# Sheet5.net
KiCad netlist of a schematic drawn in Altium Designer
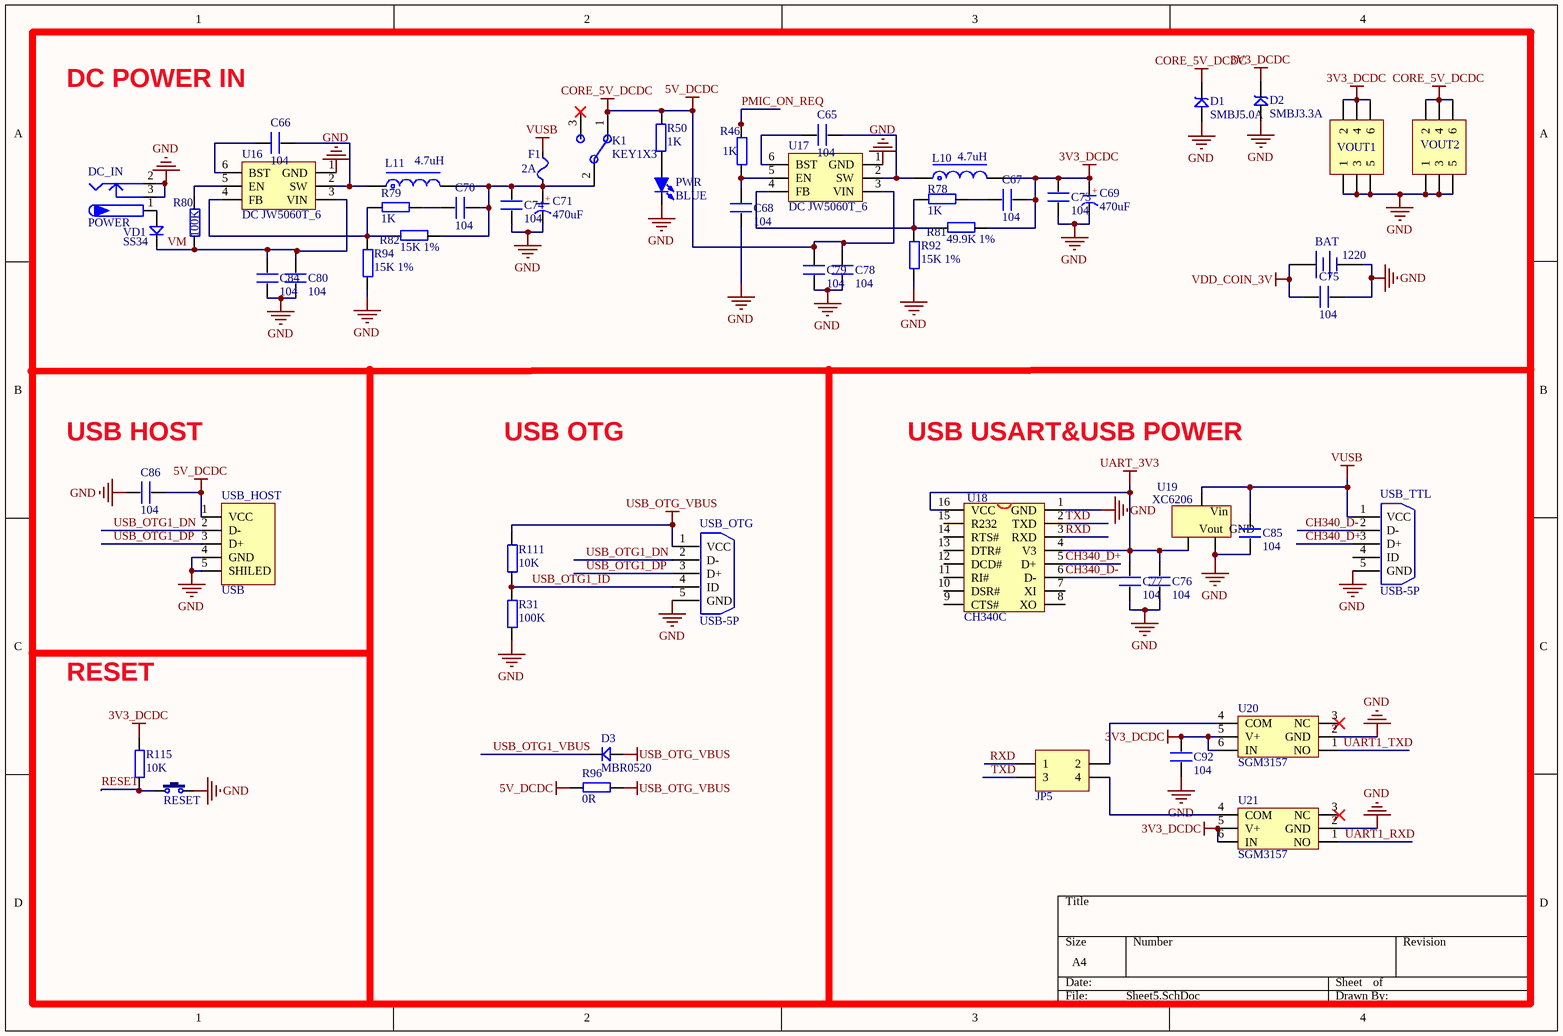
[diagram p0: Sheet5.SchDoc]

(export (version "E")
  (design (tool "Eeschema 10.0.6"))
  (components
    (comp (ref "BAT")
      (value "1220")
      (footprint "CR1220_B")
      (description "微型电池")
      (fields (field (name "版权归属") "源创客"))
      (libsource (lib "linux_board_SCH") (part "CR-3V"))
    )
    (comp (ref "C65") (value "104") (footprint "C 0603") (libsource (lib "linux_board_SCH") (part "C")))
    (comp (ref "C66") (value "104") (footprint "C 0603") (libsource (lib "linux_board_SCH") (part "C")))
    (comp (ref "C67") (value "104") (footprint "C 0603") (libsource (lib "linux_board_SCH") (part "C")))
    (comp (ref "C68") (value "104") (footprint "C 0603") (libsource (lib "linux_board_SCH") (part "C")))
    (comp (ref "C69")
      (value "470uF")
      (footprint "CM D(6.3*5.4)")
      (description "贴片电解电容")
      (fields (field (name "版权归属") "源创客"))
      (libsource (lib "linux_board_SCH") (part "C-CM"))
    )
    (comp (ref "C70") (value "104") (footprint "C 0603") (libsource (lib "linux_board_SCH") (part "C")))
    (comp (ref "C71")
      (value "470uF")
      (footprint "CM D(6.3*5.4)")
      (description "贴片电解电容")
      (fields (field (name "版权归属") "源创客"))
      (libsource (lib "linux_board_SCH") (part "C-CM"))
    )
    (comp (ref "C73") (value "104") (footprint "C 0603") (libsource (lib "linux_board_SCH") (part "C")))
    (comp (ref "C74") (value "104") (footprint "C 0603") (libsource (lib "linux_board_SCH") (part "C")))
    (comp (ref "C75") (value "104") (footprint "C 0603") (libsource (lib "linux_board_SCH") (part "C")))
    (comp (ref "C76") (value "104") (footprint "C 0603") (libsource (lib "linux_board_SCH") (part "C")))
    (comp (ref "C77") (value "104") (footprint "C 0603") (libsource (lib "linux_board_SCH") (part "C")))
    (comp (ref "C78") (value "104") (footprint "C 0603") (libsource (lib "linux_board_SCH") (part "C")))
    (comp (ref "C79") (value "104") (footprint "C 0603") (libsource (lib "linux_board_SCH") (part "C")))
    (comp (ref "C80") (value "104") (footprint "C 0603") (libsource (lib "linux_board_SCH") (part "C")))
    (comp (ref "C84") (value "104") (footprint "C 0603") (libsource (lib "linux_board_SCH") (part "C")))
    (comp (ref "C85") (value "104") (footprint "C 0603") (libsource (lib "linux_board_SCH") (part "C")))
    (comp (ref "C86") (value "104") (footprint "C 0603") (libsource (lib "linux_board_SCH") (part "C")))
    (comp (ref "C92") (value "104") (footprint "C 0603") (libsource (lib "linux_board_SCH") (part "C")))
    (comp (ref "D1")
      (value "SMBJ5.0A")
      (footprint "SMBJ")
      (description "TVS")
      (libsource (lib "linux_board_SCH") (part "SMBJ"))
    )
    (comp (ref "D2")
      (value "SMBJ3.3A")
      (footprint "SMBJ")
      (description "TVS")
      (libsource (lib "linux_board_SCH") (part "SMBJ"))
    )
    (comp (ref "D3")
      (value "MBR0520")
      (footprint "SOD-123F")
      (description "肖特基二极管")
      (fields (field (name "版权归属") "源创客"))
      (libsource (lib "linux_board_SCH") (part "SS14"))
    )
    (comp (ref "DC_IN")
      (value "POWER")
      (footprint "DC10B")
      (description "低压电源接口")
      (fields (field (name "版权归属") "源创客"))
      (libsource (lib "linux_board_SCH") (part "P-DC"))
    )
    (comp (ref "F1")
      (value "2A")
      (footprint "FU 1206")
      (description "贴片保险丝")
      (fields (field (name "版权归属") "源创客"))
      (libsource (lib "linux_board_SCH") (part "FU"))
    )
    (comp (ref "JP5")
      (value "Header2X2")
      (footprint "HDR-2X2")
      (description "2*2P接插件")
      (fields (field (name "版权归属") "源创客"))
      (libsource (lib "linux_board_SCH") (part "Header 2X2"))
    )
    (comp (ref "K1") (value "KEY1X3") (footprint "PKEY") (libsource (lib "linux_board_SCH") (part "PKEY")))
    (comp (ref "L10")
      (value "4.7uH")
      (footprint "L-SMD-0420")
      (description "功率屏蔽电感")
      (fields (field (name "版权归属") "源创客"))
      (libsource (lib "linux_board_SCH") (part "L-CDRH"))
    )
    (comp (ref "L11")
      (value "4.7uH")
      (footprint "L-SMD-0420")
      (description "功率屏蔽电感")
      (fields (field (name "版权归属") "源创客"))
      (libsource (lib "linux_board_SCH") (part "L-CDRH"))
    )
    (comp (ref "PWR")
      (value "BLUE")
      (footprint "LED 0805R")
      (description "贴片LED")
      (fields (field (name "版权归属") "源创客"))
      (libsource (lib "linux_board_SCH") (part "LED-SMD"))
    )
    (comp (ref "R31") (value "100K") (footprint "R 0603") (libsource (lib "linux_board_SCH") (part "R")))
    (comp (ref "R46") (value "1K") (footprint "R 0603") (libsource (lib "linux_board_SCH") (part "R")))
    (comp (ref "R50") (value "1K") (footprint "R 0603") (libsource (lib "linux_board_SCH") (part "R")))
    (comp (ref "R78") (value "1K") (footprint "R 0603") (libsource (lib "linux_board_SCH") (part "R")))
    (comp (ref "R79") (value "1K") (footprint "R 0603") (libsource (lib "linux_board_SCH") (part "R")))
    (comp (ref "R80") (value "100K") (footprint "R 0603") (libsource (lib "linux_board_SCH") (part "R")))
    (comp (ref "R81") (value "49.9K 1%") (footprint "R 0603") (libsource (lib "linux_board_SCH") (part "R")))
    (comp (ref "R82") (value "15K 1%") (footprint "R 0603") (libsource (lib "linux_board_SCH") (part "R")))
    (comp (ref "R92") (value "15K 1%") (footprint "R 0603") (libsource (lib "linux_board_SCH") (part "R")))
    (comp (ref "R94") (value "15K 1%") (footprint "R 0603") (libsource (lib "linux_board_SCH") (part "R")))
    (comp (ref "R96") (value "0R") (footprint "R 0603") (libsource (lib "linux_board_SCH") (part "R")))
    (comp (ref "R111") (value "10K") (footprint "R 0603") (libsource (lib "linux_board_SCH") (part "R")))
    (comp (ref "R115") (value "10K") (footprint "R 0603") (libsource (lib "linux_board_SCH") (part "R")))
    (comp (ref "RESET")
      (value "KEY")
      (footprint "TSW DIP-6*6*5 - 2")
      (description "按键")
      (fields (field (name "版权归属") "源创客"))
      (libsource (lib "linux_board_SCH") (part "KEY"))
    )
    (comp (ref "U16")
      (value "DC JW5060T_6")
      (footprint "SOT23-6N")
      (description "DC降压芯片")
      (libsource (lib "linux_board_SCH") (part "DC JW5060T_6"))
    )
    (comp (ref "U17")
      (value "DC JW5060T_6")
      (footprint "SOT23-6N")
      (description "DC降压芯片")
      (libsource (lib "linux_board_SCH") (part "DC JW5060T_6"))
    )
    (comp (ref "U18")
      (value "CH340C")
      (footprint "SOP16_N")
      (description "USB2UART")
      (libsource (lib "linux_board_SCH") (part "CH340G"))
    )
    (comp (ref "U19")
      (value "XC6206")
      (footprint "SOT23-3N")
      (description "LDO")
      (libsource (lib "linux_board_SCH") (part "LDO XC6206"))
    )
    (comp (ref "U20")
      (value "SGM3157")
      (footprint "SOT363-6L")
      (description "单路双掷模拟开关")
      (libsource (lib "linux_board_SCH") (part "SGM3157"))
    )
    (comp (ref "U21")
      (value "SGM3157")
      (footprint "SOT363-6L")
      (description "单路双掷模拟开关")
      (libsource (lib "linux_board_SCH") (part "SGM3157"))
    )
    (comp (ref "USB_HOST")
      (value "USB")
      (footprint "USB-A/S_E")
      (description "USB-A型母接口")
      (fields (field (name "版权归属") "源创客"))
      (libsource (lib "linux_board_SCH") (part "USB-A/S"))
    )
    (comp (ref "USB_OTG")
      (value "USB-5P")
      (footprint "USB-MINI-A")
      (description "微型USB母座")
      (fields (field (name "版权归属") "源创客"))
      (libsource (lib "linux_board_SCH") (part "USB-5P"))
    )
    (comp (ref "USB_TTL")
      (value "USB-5P")
      (footprint "USB-MINI-A")
      (description "微型USB母座")
      (fields (field (name "版权归属") "源创客"))
      (libsource (lib "linux_board_SCH") (part "USB-5P"))
    )
    (comp (ref "VD1")
      (value "SS34")
      (footprint "SOD323")
      (description "肖特基二极管")
      (fields (field (name "版权归属") "源创客"))
      (libsource (lib "linux_board_SCH") (part "SS14"))
    )
    (comp (ref "VOUT1")
      (value "RS232/RS485")
      (footprint "HDR-3X2")
      (description "3*2P接插件")
      (fields (field (name "版权归属") "源创客"))
      (libsource (lib "linux_board_SCH") (part "Header 3X2"))
    )
    (comp (ref "VOUT2")
      (value "RS232/RS485")
      (footprint "HDR-3X2")
      (description "3*2P接插件")
      (fields (field (name "版权归属") "源创客"))
      (libsource (lib "linux_board_SCH") (part "Header 3X2"))
    )
  )
  (nets
    (net (code "1") (name "/CH340_D+") (class "Default")
      (node (ref "U18") (pin "5") (pinfunction "D+_5") (pintype "passive"))
      (node (ref "USB_TTL") (pin "3") (pinfunction "D+_3") (pintype "passive"))
    )
    (net (code "2") (name "/CH340_D-") (class "Default")
      (node (ref "U18") (pin "6") (pinfunction "D-_6") (pintype "passive"))
      (node (ref "USB_TTL") (pin "2") (pinfunction "D-_2") (pintype "passive"))
    )
    (net (code "3") (name "/PMIC_ON_REQ") (class "Default") (node (ref "R46") (pin "2") (pintype "passive")))
    (net (code "4") (name "/RESET") (class "Default")
      (node (ref "R115") (pin "1") (pintype "passive"))
      (node (ref "RESET") (pin "1") (pinfunction "1_1") (pintype "passive"))
    )
    (net (code "5") (name "/RXD") (class "Default")
      (node (ref "JP5") (pin "1") (pinfunction "1_1") (pintype "passive"))
      (node (ref "U18") (pin "3") (pinfunction "RXD_3") (pintype "passive"))
    )
    (net (code "6") (name "/TXD") (class "Default")
      (node (ref "JP5") (pin "3") (pinfunction "3_3") (pintype "passive"))
      (node (ref "U18") (pin "2") (pinfunction "TXD_2") (pintype "passive"))
    )
    (net (code "7") (name "/UART1_RXD") (class "Default")
      (node (ref "U21") (pin "1") (pinfunction "NO_1") (pintype "passive"))
    )
    (net (code "8") (name "/UART1_TXD") (class "Default")
      (node (ref "U20") (pin "1") (pinfunction "NO_1") (pintype "passive"))
    )
    (net (code "9") (name "/USB_OTG1_DN") (class "Default")
      (node (ref "USB_HOST") (pin "2") (pinfunction "D-_2") (pintype "passive"))
      (node (ref "USB_OTG") (pin "2") (pinfunction "D-_2") (pintype "passive"))
    )
    (net (code "10") (name "/USB_OTG1_DP") (class "Default")
      (node (ref "USB_HOST") (pin "3") (pinfunction "D+_3") (pintype "passive"))
      (node (ref "USB_OTG") (pin "3") (pinfunction "D+_3") (pintype "passive"))
    )
    (net (code "11") (name "/USB_OTG1_ID") (class "Default")
      (node (ref "R111") (pin "1") (pintype "passive"))
      (node (ref "R31") (pin "2") (pintype "passive"))
      (node (ref "USB_OTG") (pin "4") (pinfunction "ID_4") (pintype "passive"))
    )
    (net (code "12") (name "/USB_OTG1_VBUS") (class "Default")
      (node (ref "D3") (pin "2") (pinfunction "K_2") (pintype "passive"))
    )
    (net (code "13") (name "/VM") (class "Default")
      (node (ref "C80") (pin "2") (pinfunction "2_2") (pintype "passive"))
      (node (ref "C84") (pin "2") (pinfunction "2_2") (pintype "passive"))
      (node (ref "R80") (pin "1") (pintype "passive"))
      (node (ref "U16") (pin "3") (pinfunction "VIN_3") (pintype "passive"))
      (node (ref "VD1") (pin "2") (pinfunction "K_2") (pintype "passive"))
    )
    (net (code "14") (name "3V3_DCDC") (class "Default")
      (node (ref "C67") (pin "2") (pinfunction "2_2") (pintype "passive"))
      (node (ref "C69") (pin "1") (pinfunction "A_1") (pintype "passive"))
      (node (ref "C73") (pin "2") (pinfunction "2_2") (pintype "passive"))
      (node (ref "C92") (pin "2") (pinfunction "2_2") (pintype "passive"))
      (node (ref "D2") (pin "2") (pintype "passive"))
      (node (ref "L10") (pin "2") (pinfunction "2_2") (pintype "passive"))
      (node (ref "R115") (pin "2") (pintype "passive"))
      (node (ref "R81") (pin "1") (pintype "passive"))
      (node (ref "U20") (pin "5") (pinfunction "V+_5") (pintype "passive"))
      (node (ref "U20") (pin "6") (pinfunction "IN_6") (pintype "passive"))
      (node (ref "U21") (pin "5") (pinfunction "V+_5") (pintype "passive"))
      (node (ref "U21") (pin "6") (pinfunction "IN_6") (pintype "passive"))
      (node (ref "VOUT1") (pin "2") (pinfunction "2_2") (pintype "passive"))
      (node (ref "VOUT1") (pin "4") (pinfunction "4_4") (pintype "passive"))
      (node (ref "VOUT1") (pin "6") (pinfunction "6_6") (pintype "passive"))
    )
    (net (code "15") (name "5V_DCDC") (class "Default")
      (node (ref "C78") (pin "2") (pinfunction "2_2") (pintype "passive"))
      (node (ref "C79") (pin "2") (pinfunction "2_2") (pintype "passive"))
      (node (ref "C86") (pin "1") (pinfunction "1_1") (pintype "passive"))
      (node (ref "D1") (pin "2") (pintype "passive"))
      (node (ref "K1") (pin "1") (pintype "passive"))
      (node (ref "R50") (pin "1") (pintype "passive"))
      (node (ref "R96") (pin "2") (pintype "passive"))
      (node (ref "U17") (pin "3") (pinfunction "VIN_3") (pintype "passive"))
      (node (ref "USB_HOST") (pin "1") (pinfunction "VCC_1") (pintype "passive"))
      (node (ref "VOUT2") (pin "2") (pinfunction "2_2") (pintype "passive"))
      (node (ref "VOUT2") (pin "4") (pinfunction "4_4") (pintype "passive"))
      (node (ref "VOUT2") (pin "6") (pinfunction "6_6") (pintype "passive"))
    )
    (net (code "16") (name "GND") (class "Default")
      (node (ref "BAT") (pin "2") (pinfunction "DC-_2") (pintype "passive"))
      (node (ref "C68") (pin "1") (pinfunction "1_1") (pintype "passive"))
      (node (ref "C69") (pin "2") (pinfunction "K_2") (pintype "passive"))
      (node (ref "C71") (pin "2") (pinfunction "K_2") (pintype "passive"))
      (node (ref "C73") (pin "1") (pinfunction "1_1") (pintype "passive"))
      (node (ref "C74") (pin "1") (pinfunction "1_1") (pintype "passive"))
      (node (ref "C75") (pin "2") (pinfunction "2_2") (pintype "passive"))
      (node (ref "C76") (pin "1") (pinfunction "1_1") (pintype "passive"))
      (node (ref "C77") (pin "1") (pinfunction "1_1") (pintype "passive"))
      (node (ref "C78") (pin "1") (pinfunction "1_1") (pintype "passive"))
      (node (ref "C79") (pin "1") (pinfunction "1_1") (pintype "passive"))
      (node (ref "C80") (pin "1") (pinfunction "1_1") (pintype "passive"))
      (node (ref "C84") (pin "1") (pinfunction "1_1") (pintype "passive"))
      (node (ref "C85") (pin "1") (pinfunction "1_1") (pintype "passive"))
      (node (ref "C86") (pin "2") (pinfunction "2_2") (pintype "passive"))
      (node (ref "C92") (pin "1") (pinfunction "1_1") (pintype "passive"))
      (node (ref "D1") (pin "1") (pintype "passive"))
      (node (ref "D2") (pin "1") (pintype "passive"))
      (node (ref "DC_IN") (pin "2") (pintype "power_in"))
      (node (ref "DC_IN") (pin "3") (pintype "power_in"))
      (node (ref "PWR") (pin "2") (pinfunction "K_2") (pintype "passive"))
      (node (ref "R31") (pin "1") (pintype "passive"))
      (node (ref "R92") (pin "1") (pintype "passive"))
      (node (ref "R94") (pin "1") (pintype "passive"))
      (node (ref "RESET") (pin "2") (pinfunction "2_2") (pintype "passive"))
      (node (ref "U16") (pin "1") (pinfunction "GND_1") (pintype "passive"))
      (node (ref "U17") (pin "1") (pinfunction "GND_1") (pintype "passive"))
      (node (ref "U18") (pin "1") (pinfunction "GND_1") (pintype "passive"))
      (node (ref "U19") (pin "1") (pinfunction "GND_1") (pintype "passive"))
      (node (ref "U20") (pin "2") (pinfunction "GND_2") (pintype "passive"))
      (node (ref "U21") (pin "2") (pinfunction "GND_2") (pintype "passive"))
      (node (ref "USB_HOST") (pin "4") (pinfunction "GND_4") (pintype "passive"))
      (node (ref "USB_HOST") (pin "5") (pinfunction "SHILED_5") (pintype "passive"))
      (node (ref "USB_OTG") (pin "5") (pinfunction "GND_5") (pintype "passive"))
      (node (ref "USB_TTL") (pin "5") (pinfunction "GND_5") (pintype "passive"))
      (node (ref "VOUT1") (pin "1") (pinfunction "1_1") (pintype "passive"))
      (node (ref "VOUT1") (pin "3") (pinfunction "3_3") (pintype "passive"))
      (node (ref "VOUT1") (pin "5") (pinfunction "5_5") (pintype "passive"))
      (node (ref "VOUT2") (pin "1") (pinfunction "1_1") (pintype "passive"))
      (node (ref "VOUT2") (pin "3") (pinfunction "3_3") (pintype "passive"))
      (node (ref "VOUT2") (pin "5") (pinfunction "5_5") (pintype "passive"))
    )
    (net (code "17") (name "Net-(C67-Pad1)") (class "Default")
      (node (ref "C67") (pin "1") (pinfunction "1_1") (pintype "passive"))
      (node (ref "R78") (pin "1") (pintype "passive"))
    )
    (net (code "18") (name "Net-(C70-Pad1)") (class "Default")
      (node (ref "C70") (pin "1") (pinfunction "1_1") (pintype "passive"))
      (node (ref "R79") (pin "1") (pintype "passive"))
    )
    (net (code "19") (name "Net-(C71-A)") (class "Default")
      (node (ref "C70") (pin "2") (pinfunction "2_2") (pintype "passive"))
      (node (ref "C71") (pin "1") (pinfunction "A_1") (pintype "passive"))
      (node (ref "C74") (pin "2") (pinfunction "2_2") (pintype "passive"))
      (node (ref "F1") (pin "1") (pinfunction "1_1") (pintype "passive"))
      (node (ref "K1") (pin "2") (pintype "passive"))
      (node (ref "L11") (pin "2") (pinfunction "2_2") (pintype "passive"))
      (node (ref "R82") (pin "1") (pintype "passive"))
    )
    (net (code "20") (name "Net-(PWR-A)") (class "Default")
      (node (ref "PWR") (pin "1") (pinfunction "A_1") (pintype "passive"))
      (node (ref "R50") (pin "2") (pintype "passive"))
    )
    (net (code "21") (name "Net-(U16-BST)") (class "Default")
      (node (ref "C66") (pin "1") (pinfunction "1_1") (pintype "passive"))
      (node (ref "U16") (pin "6") (pinfunction "BST_6") (pintype "passive"))
    )
    (net (code "22") (name "Net-(U16-EN)") (class "Default")
      (node (ref "R80") (pin "2") (pintype "passive"))
      (node (ref "U16") (pin "5") (pinfunction "EN_5") (pintype "passive"))
    )
    (net (code "23") (name "Net-(U16-FB)") (class "Default")
      (node (ref "R79") (pin "2") (pintype "passive"))
      (node (ref "R82") (pin "2") (pintype "passive"))
      (node (ref "R94") (pin "2") (pintype "passive"))
      (node (ref "U16") (pin "4") (pinfunction "FB_4") (pintype "passive"))
    )
    (net (code "24") (name "Net-(U16-SW)") (class "Default")
      (node (ref "C66") (pin "2") (pinfunction "2_2") (pintype "passive"))
      (node (ref "L11") (pin "1") (pinfunction "1_1") (pintype "passive"))
      (node (ref "U16") (pin "2") (pinfunction "SW_2") (pintype "passive"))
    )
    (net (code "25") (name "Net-(U17-BST)") (class "Default")
      (node (ref "C65") (pin "1") (pinfunction "1_1") (pintype "passive"))
      (node (ref "U17") (pin "6") (pinfunction "BST_6") (pintype "passive"))
    )
    (net (code "26") (name "Net-(U17-EN)") (class "Default")
      (node (ref "C68") (pin "2") (pinfunction "2_2") (pintype "passive"))
      (node (ref "R46") (pin "1") (pintype "passive"))
      (node (ref "U17") (pin "5") (pinfunction "EN_5") (pintype "passive"))
    )
    (net (code "27") (name "Net-(U17-FB)") (class "Default")
      (node (ref "R78") (pin "2") (pintype "passive"))
      (node (ref "R81") (pin "2") (pintype "passive"))
      (node (ref "R92") (pin "2") (pintype "passive"))
      (node (ref "U17") (pin "4") (pinfunction "FB_4") (pintype "passive"))
    )
    (net (code "28") (name "Net-(U17-SW)") (class "Default")
      (node (ref "C65") (pin "2") (pinfunction "2_2") (pintype "passive"))
      (node (ref "L10") (pin "1") (pinfunction "1_1") (pintype "passive"))
      (node (ref "U17") (pin "2") (pinfunction "SW_2") (pintype "passive"))
    )
    (net (code "29") (name "Net-(U20-COM)") (class "Default")
      (node (ref "JP5") (pin "2") (pinfunction "2_2") (pintype "passive"))
      (node (ref "U20") (pin "4") (pinfunction "COM_4") (pintype "passive"))
    )
    (net (code "30") (name "Net-(U21-COM)") (class "Default")
      (node (ref "JP5") (pin "4") (pinfunction "4_4") (pintype "passive"))
      (node (ref "U21") (pin "4") (pinfunction "COM_4") (pintype "passive"))
    )
    (net (code "31") (name "Net-(VD1-A)") (class "Default")
      (node (ref "DC_IN") (pin "1") (pintype "power_in"))
      (node (ref "VD1") (pin "1") (pinfunction "A_1") (pintype "passive"))
    )
    (net (code "32") (name "UART_3V3") (class "Default")
      (node (ref "C76") (pin "2") (pinfunction "2_2") (pintype "passive"))
      (node (ref "C77") (pin "2") (pinfunction "2_2") (pintype "passive"))
      (node (ref "U18") (pin "16") (pinfunction "VCC_16") (pintype "passive"))
      (node (ref "U18") (pin "4") (pinfunction "V3_4") (pintype "passive"))
      (node (ref "U19") (pin "2") (pinfunction "Vout_2") (pintype "passive"))
    )
    (net (code "33") (name "USB_OTG_VBUS") (class "Default")
      (node (ref "D3") (pin "1") (pinfunction "A_1") (pintype "passive"))
      (node (ref "R111") (pin "2") (pintype "passive"))
      (node (ref "R96") (pin "1") (pintype "passive"))
      (node (ref "USB_OTG") (pin "1") (pinfunction "VCC_1") (pintype "passive"))
    )
    (net (code "34") (name "VDD_COIN_3V") (class "Default")
      (node (ref "BAT") (pin "1") (pinfunction "DC+_1") (pintype "passive"))
      (node (ref "C75") (pin "1") (pinfunction "1_1") (pintype "passive"))
    )
    (net (code "35") (name "VUSB") (class "Default")
      (node (ref "C85") (pin "2") (pinfunction "2_2") (pintype "passive"))
      (node (ref "F1") (pin "2") (pinfunction "2_2") (pintype "passive"))
      (node (ref "U19") (pin "3") (pinfunction "Vin_3") (pintype "passive"))
      (node (ref "USB_TTL") (pin "1") (pinfunction "VCC_1") (pintype "passive"))
    )
    (net (code "36") (name "unconnected-(K1-Pad3)") (class "Default")
      (node (ref "K1") (pin "3") (pintype "passive+no_connect"))
    )
    (net (code "37") (name "unconnected-(U18-CTS#-Pad9)") (class "Default")
      (node (ref "U18") (pin "9") (pinfunction "CTS#_9") (pintype "passive"))
    )
    (net (code "38") (name "unconnected-(U18-DCD#-Pad12)") (class "Default")
      (node (ref "U18") (pin "12") (pinfunction "DCD#_12") (pintype "passive"))
    )
    (net (code "39") (name "unconnected-(U18-DSR#-Pad10)") (class "Default")
      (node (ref "U18") (pin "10") (pinfunction "DSR#_10") (pintype "passive"))
    )
    (net (code "40") (name "unconnected-(U18-DTR#-Pad13)") (class "Default")
      (node (ref "U18") (pin "13") (pinfunction "DTR#_13") (pintype "passive"))
    )
    (net (code "41") (name "unconnected-(U18-R232-Pad15)") (class "Default")
      (node (ref "U18") (pin "15") (pinfunction "R232_15") (pintype "passive"))
    )
    (net (code "42") (name "unconnected-(U18-RI#-Pad11)") (class "Default")
      (node (ref "U18") (pin "11") (pinfunction "RI#_11") (pintype "passive"))
    )
    (net (code "43") (name "unconnected-(U18-RTS#-Pad14)") (class "Default")
      (node (ref "U18") (pin "14") (pinfunction "RTS#_14") (pintype "passive"))
    )
    (net (code "44") (name "unconnected-(U18-XI-Pad7)") (class "Default")
      (node (ref "U18") (pin "7") (pinfunction "XI_7") (pintype "passive"))
    )
    (net (code "45") (name "unconnected-(U18-XO-Pad8)") (class "Default")
      (node (ref "U18") (pin "8") (pinfunction "XO_8") (pintype "passive"))
    )
    (net (code "46") (name "unconnected-(U20-NC-Pad3)") (class "Default")
      (node (ref "U20") (pin "3") (pinfunction "NC_3") (pintype "passive+no_connect"))
    )
    (net (code "47") (name "unconnected-(U21-NC-Pad3)") (class "Default")
      (node (ref "U21") (pin "3") (pinfunction "NC_3") (pintype "passive+no_connect"))
    )
    (net (code "48") (name "unconnected-(USB_TTL-ID-Pad4)") (class "Default")
      (node (ref "USB_TTL") (pin "4") (pinfunction "ID_4") (pintype "passive"))
    )
  )
)
